# ECG_Combined.net
KiCad netlist of a schematic drawn in EAGLE
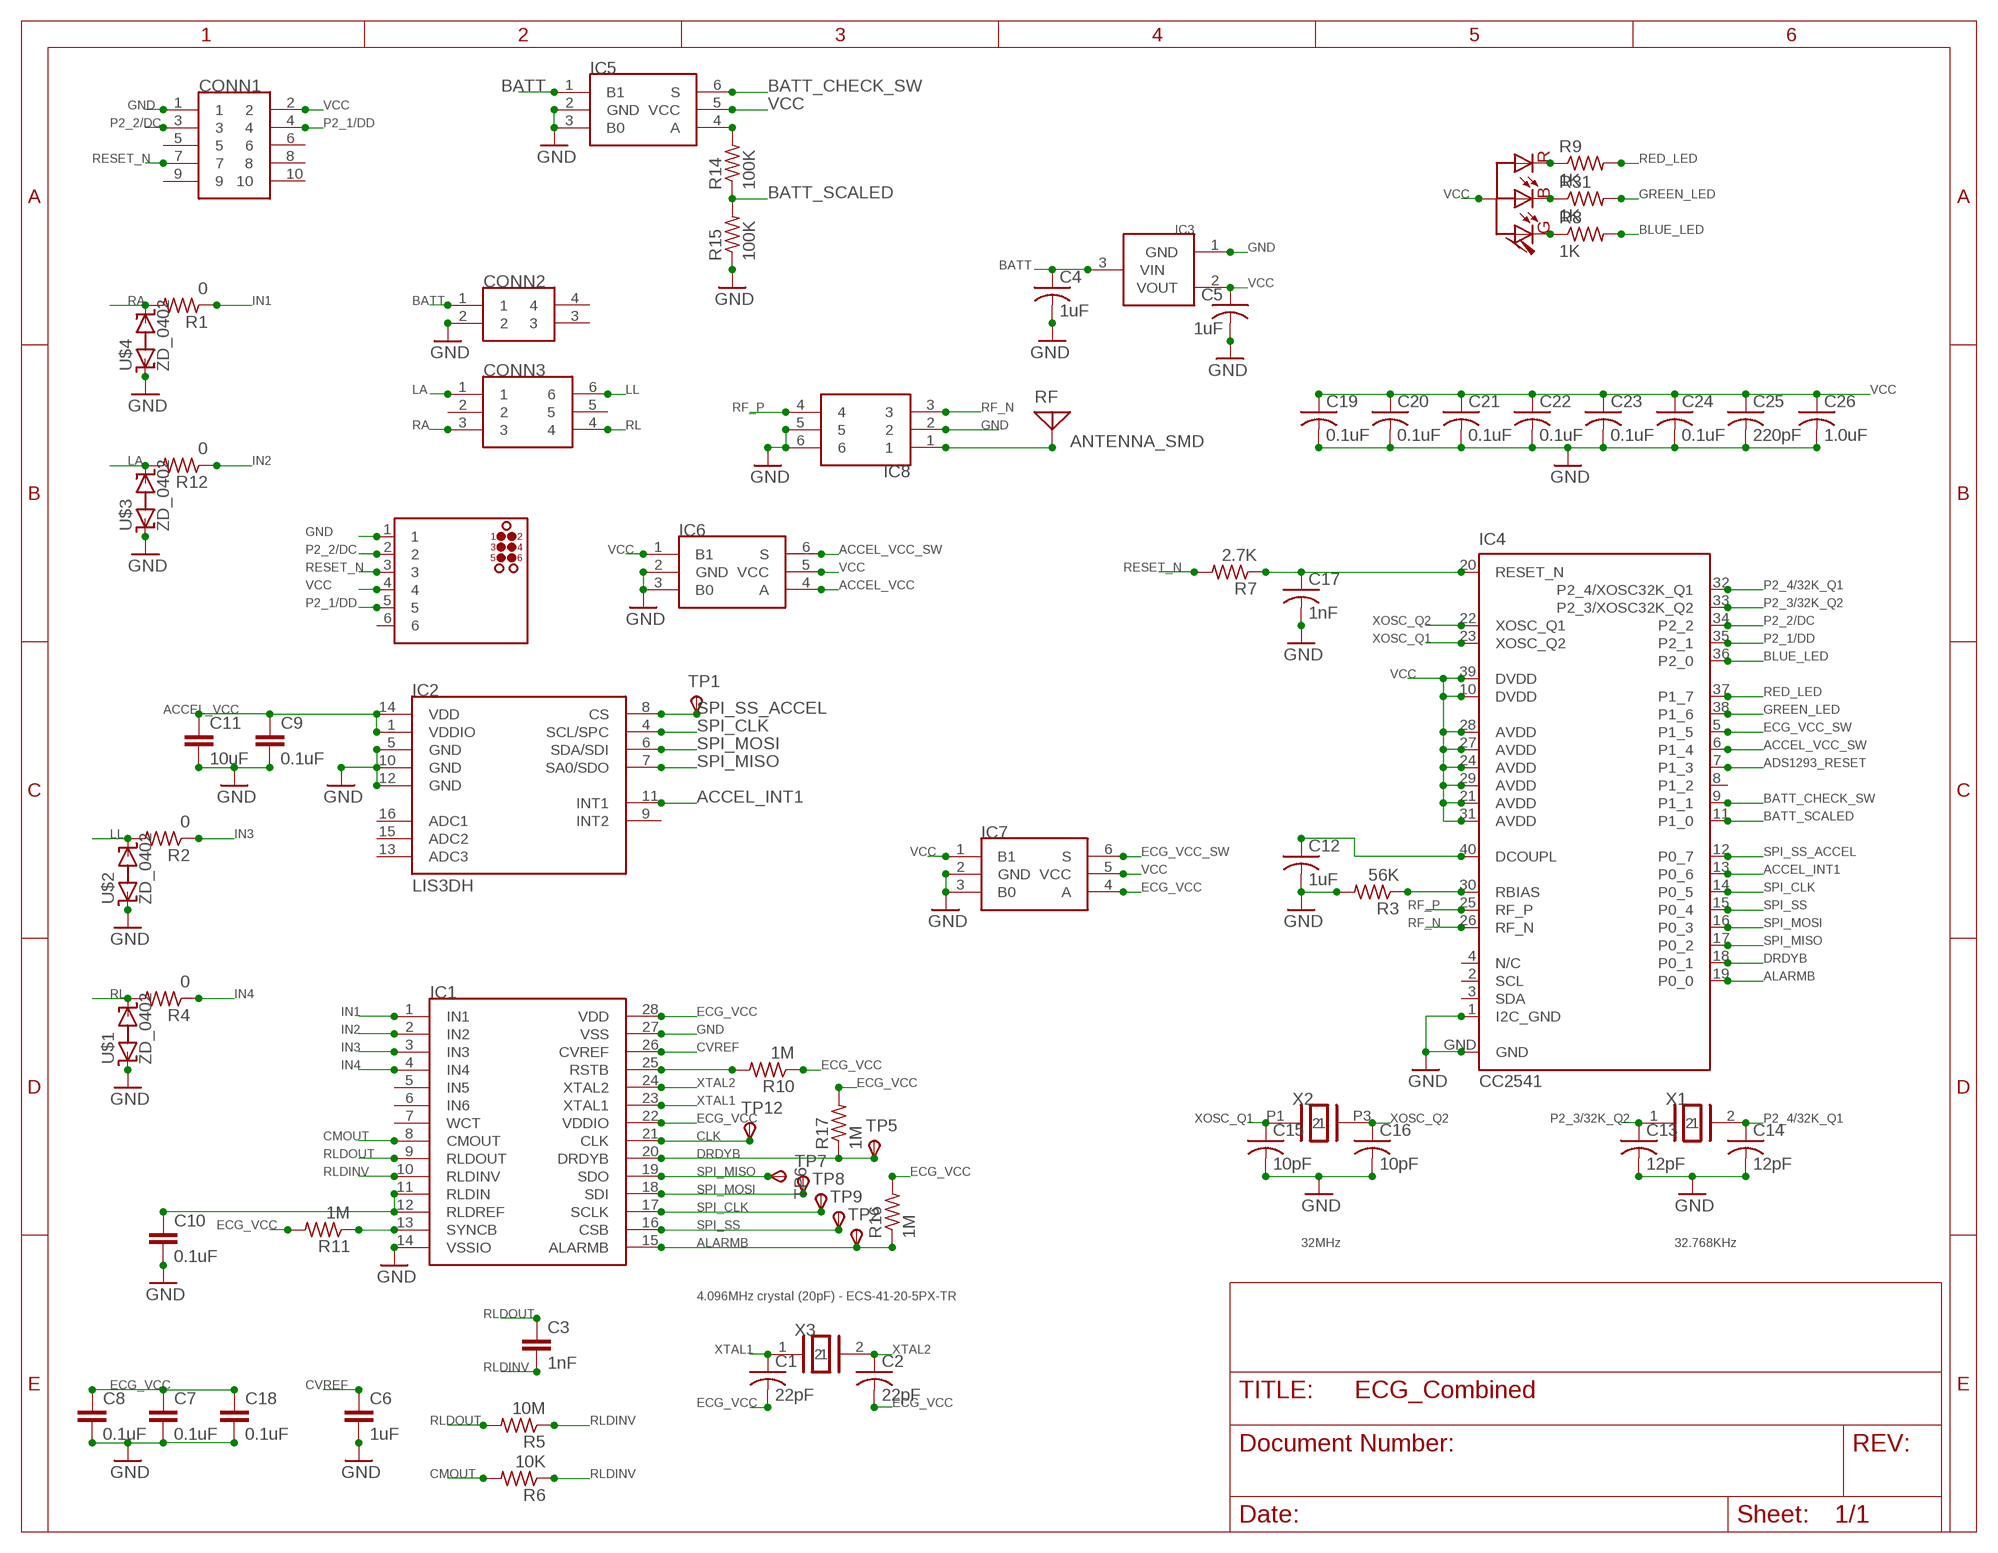
[diagram p0: schematic, sheet 1]

(export (version "E")
  (design (tool "Eeschema 10.0.6"))
  (components
    (comp (ref "C1")
      (value "22pF")
      (footprint "eagle-import:C0201")
      (libsource (lib "eagle-import") (part "C-USC0201"))
    )
    (comp (ref "C2")
      (value "22pF")
      (footprint "eagle-import:C0201")
      (libsource (lib "eagle-import") (part "C-USC0201"))
    )
    (comp (ref "C3")
      (value "1nF")
      (footprint "eagle-import:C0201")
      (libsource (lib "eagle-import") (part "C-EUC0201"))
    )
    (comp (ref "C4")
      (value "1uF")
      (footprint "eagle-import:C0201")
      (libsource (lib "eagle-import") (part "C-USC0201"))
    )
    (comp (ref "C5")
      (value "1uF")
      (footprint "eagle-import:C0201")
      (libsource (lib "eagle-import") (part "C-USC0201"))
    )
    (comp (ref "C6")
      (value "1uF")
      (footprint "eagle-import:C0201")
      (libsource (lib "eagle-import") (part "C-EUC0201"))
    )
    (comp (ref "C7")
      (value "0.1uF")
      (footprint "eagle-import:C0201")
      (libsource (lib "eagle-import") (part "C-EUC0201"))
    )
    (comp (ref "C8")
      (value "0.1uF")
      (footprint "eagle-import:C0201")
      (libsource (lib "eagle-import") (part "C-EUC0201"))
    )
    (comp (ref "C9")
      (value "0.1uF")
      (footprint "eagle-import:C0201")
      (libsource (lib "eagle-import") (part "C-EUC0201"))
    )
    (comp (ref "C10")
      (value "0.1uF")
      (footprint "eagle-import:C0201")
      (libsource (lib "eagle-import") (part "C-EUC0201"))
    )
    (comp (ref "C11")
      (value "10uF")
      (footprint "eagle-import:C0402")
      (libsource (lib "eagle-import") (part "C-EUC0402"))
    )
    (comp (ref "C12")
      (value "1uF")
      (footprint "eagle-import:C0201")
      (libsource (lib "eagle-import") (part "C-USC0201"))
    )
    (comp (ref "C13")
      (value "12pF")
      (footprint "eagle-import:C0201")
      (libsource (lib "eagle-import") (part "C-USC0201"))
    )
    (comp (ref "C14")
      (value "12pF")
      (footprint "eagle-import:C0201")
      (libsource (lib "eagle-import") (part "C-USC0201"))
    )
    (comp (ref "C15")
      (value "10pF")
      (footprint "eagle-import:C0201")
      (libsource (lib "eagle-import") (part "C-USC0201"))
    )
    (comp (ref "C16")
      (value "10pF")
      (footprint "eagle-import:C0201")
      (libsource (lib "eagle-import") (part "C-USC0201"))
    )
    (comp (ref "C17")
      (value "1nF")
      (footprint "eagle-import:C0201")
      (libsource (lib "eagle-import") (part "C-USC0201"))
    )
    (comp (ref "C18")
      (value "0.1uF")
      (footprint "eagle-import:C0201")
      (libsource (lib "eagle-import") (part "C-EUC0201"))
    )
    (comp (ref "C19")
      (value "0.1uF")
      (footprint "eagle-import:C0201")
      (libsource (lib "eagle-import") (part "C-USC0201"))
    )
    (comp (ref "C20")
      (value "0.1uF")
      (footprint "eagle-import:C0201")
      (libsource (lib "eagle-import") (part "C-USC0201"))
    )
    (comp (ref "C21")
      (value "0.1uF")
      (footprint "eagle-import:C0201")
      (libsource (lib "eagle-import") (part "C-USC0201"))
    )
    (comp (ref "C22")
      (value "0.1uF")
      (footprint "eagle-import:C0201")
      (libsource (lib "eagle-import") (part "C-USC0201"))
    )
    (comp (ref "C23")
      (value "0.1uF")
      (footprint "eagle-import:C0201")
      (libsource (lib "eagle-import") (part "C-USC0201"))
    )
    (comp (ref "C24")
      (value "0.1uF")
      (footprint "eagle-import:C0201")
      (libsource (lib "eagle-import") (part "C-USC0201"))
    )
    (comp (ref "C25")
      (value "220pF")
      (footprint "eagle-import:C0201")
      (libsource (lib "eagle-import") (part "C-USC0201"))
    )
    (comp (ref "C26")
      (value "1.0uF")
      (footprint "eagle-import:C0201")
      (libsource (lib "eagle-import") (part "C-USC0201"))
    )
    (comp (ref "CONN1")
      (value "10POS_1.27MM_SMD")
      (footprint "eagle-import:1.27MM_SMD")
      (libsource (lib "eagle-import") (part "10POS_1.27MM_SMD"))
    )
    (comp (ref "CONN2")
      (value "M80-4V")
      (footprint "eagle-import:M80-4-V")
      (libsource (lib "eagle-import") (part "M80-4V"))
    )
    (comp (ref "CONN3")
      (value "M80-6V")
      (footprint "eagle-import:M80-6-V")
      (libsource (lib "eagle-import") (part "M80-6V"))
    )
    (comp (ref "IC1")
      (value "ADS1293")
      (footprint "eagle-import:WQFN28")
      (libsource (lib "eagle-import") (part "ADS1293"))
    )
    (comp (ref "IC2")
      (value "LIS3DH")
      (footprint "eagle-import:LGA16-3MM")
      (libsource (lib "eagle-import") (part "LIS3DH"))
    )
    (comp (ref "IC3")
      (value "MCP1703")
      (footprint "eagle-import:SOT23")
      (libsource (lib "eagle-import") (part "MCP1703"))
    )
    (comp (ref "IC4")
      (value "CC2541")
      (footprint "eagle-import:RHA_S-PVQFN-N40")
      (libsource (lib "eagle-import") (part "CC2541"))
    )
    (comp (ref "IC5")
      (value "FSA4157")
      (footprint "eagle-import:SC70-6")
      (libsource (lib "eagle-import") (part "FSA4157"))
    )
    (comp (ref "IC6")
      (value "FSA4157")
      (footprint "eagle-import:SC70-6")
      (libsource (lib "eagle-import") (part "FSA4157"))
    )
    (comp (ref "IC7")
      (value "FSA4157")
      (footprint "eagle-import:SC70-6")
      (libsource (lib "eagle-import") (part "FSA4157"))
    )
    (comp (ref "IC8")
      (value "BALUN_2450BM_SERIES_SMD")
      (footprint "eagle-import:BALUN_SMD_2450BM_SERIES")
      (libsource (lib "eagle-import") (part "BALUN_2450BM_SERIES_SMD"))
    )
    (comp (ref "R1")
      (value "0")
      (footprint "eagle-import:R0201")
      (libsource (lib "eagle-import") (part "R-US_R0201"))
    )
    (comp (ref "R2")
      (value "0")
      (footprint "eagle-import:R0201")
      (libsource (lib "eagle-import") (part "R-US_R0201"))
    )
    (comp (ref "R3")
      (value "56K")
      (footprint "eagle-import:R0201")
      (libsource (lib "eagle-import") (part "R-US_R0201"))
    )
    (comp (ref "R4")
      (value "0")
      (footprint "eagle-import:R0201")
      (libsource (lib "eagle-import") (part "R-US_R0201"))
    )
    (comp (ref "R5")
      (value "10M")
      (footprint "eagle-import:R0201")
      (libsource (lib "eagle-import") (part "R-US_R0201"))
    )
    (comp (ref "R6")
      (value "10K")
      (footprint "eagle-import:R0201")
      (libsource (lib "eagle-import") (part "R-US_R0201"))
    )
    (comp (ref "R7")
      (value "2.7K")
      (footprint "eagle-import:R0201")
      (libsource (lib "eagle-import") (part "R-US_R0201"))
    )
    (comp (ref "R8")
      (value "1K")
      (footprint "eagle-import:R0201")
      (libsource (lib "eagle-import") (part "R-US_R0201"))
    )
    (comp (ref "R9")
      (value "1K")
      (footprint "eagle-import:R0201")
      (libsource (lib "eagle-import") (part "R-US_R0201"))
    )
    (comp (ref "R10")
      (value "1M")
      (footprint "eagle-import:R0201")
      (libsource (lib "eagle-import") (part "R-US_R0201"))
    )
    (comp (ref "R11")
      (value "1M")
      (footprint "eagle-import:R0201")
      (libsource (lib "eagle-import") (part "R-US_R0201"))
    )
    (comp (ref "R12")
      (value "0")
      (footprint "eagle-import:R0201")
      (libsource (lib "eagle-import") (part "R-US_R0201"))
    )
    (comp (ref "R14")
      (value "100K")
      (footprint "eagle-import:R0201")
      (libsource (lib "eagle-import") (part "R-US_R0201"))
    )
    (comp (ref "R15")
      (value "100K")
      (footprint "eagle-import:R0201")
      (libsource (lib "eagle-import") (part "R-US_R0201"))
    )
    (comp (ref "R16")
      (value "1M")
      (footprint "eagle-import:R0201")
      (libsource (lib "eagle-import") (part "R-US_R0201"))
    )
    (comp (ref "R17")
      (value "1M")
      (footprint "eagle-import:R0201")
      (libsource (lib "eagle-import") (part "R-US_R0201"))
    )
    (comp (ref "R31")
      (value "1K")
      (footprint "eagle-import:R0201")
      (libsource (lib "eagle-import") (part "R-US_R0201"))
    )
    (comp (ref "RF")
      (value "ANTENNA_SMD")
      (footprint "eagle-import:ANTENNA_SMD")
      (libsource (lib "eagle-import") (part "ANTENNA_SMD"))
    )
    (comp (ref "TP1")
      (value "TPSTP08SQ")
      (footprint "eagle-import:TP08SQ")
      (libsource (lib "eagle-import") (part "TPSTP08SQ"))
    )
    (comp (ref "TP2")
      (value "TPSTP06R")
      (footprint "eagle-import:TP06R")
      (libsource (lib "eagle-import") (part "TPSTP06R"))
    )
    (comp (ref "TP5")
      (value "TPSTP08SQ")
      (footprint "eagle-import:TP08SQ")
      (libsource (lib "eagle-import") (part "TPSTP08SQ"))
    )
    (comp (ref "TP6")
      (value "TPSTP08SQ")
      (footprint "eagle-import:TP08SQ")
      (libsource (lib "eagle-import") (part "TPSTP08SQ"))
    )
    (comp (ref "TP7")
      (value "TPSTP08SQ")
      (footprint "eagle-import:TP08SQ")
      (libsource (lib "eagle-import") (part "TPSTP08SQ"))
    )
    (comp (ref "TP8")
      (value "TPSTP08SQ")
      (footprint "eagle-import:TP08SQ")
      (libsource (lib "eagle-import") (part "TPSTP08SQ"))
    )
    (comp (ref "TP9")
      (value "TPSTP08SQ")
      (footprint "eagle-import:TP08SQ")
      (libsource (lib "eagle-import") (part "TPSTP08SQ"))
    )
    (comp (ref "TP12")
      (value "TPSTP06R")
      (footprint "eagle-import:TP06R")
      (libsource (lib "eagle-import") (part "TPSTP06R"))
    )
    (comp (ref "TRI_LED")
      (value "SML-LX0404SIUPGUSB")
      (footprint "eagle-import:SML-LX0404SIUPGUSB")
      (libsource (lib "eagle-import") (part "SML-LX0404SIUPGUSB"))
    )
    (comp (ref "U$1")
      (value "ZD_0402")
      (footprint "eagle-import:0402")
      (libsource (lib "eagle-import") (part "ZD_0402"))
    )
    (comp (ref "U$2")
      (value "ZD_0402")
      (footprint "eagle-import:0402")
      (libsource (lib "eagle-import") (part "ZD_0402"))
    )
    (comp (ref "U$3")
      (value "ZD_0402")
      (footprint "eagle-import:0402")
      (libsource (lib "eagle-import") (part "ZD_0402"))
    )
    (comp (ref "U$4")
      (value "ZD_0402")
      (footprint "eagle-import:0402")
      (libsource (lib "eagle-import") (part "ZD_0402"))
    )
    (comp (ref "U$5")
      (value "TC2030-MCP-NL")
      (footprint "eagle-import:TC2030-MCP-NL")
      (libsource (lib "eagle-import") (part "TC2030-MCP-NL"))
    )
    (comp (ref "X1")
      (value "XTAL-2SMD")
      (footprint "eagle-import:2-SMD")
      (libsource (lib "eagle-import") (part "XTAL-2SMD"))
    )
    (comp (ref "X2")
      (value "XTAL_403")
      (footprint "eagle-import:4-SMD")
      (libsource (lib "eagle-import") (part "XTAL_403"))
    )
    (comp (ref "X3")
      (value "XTAL-CSM7")
      (footprint "eagle-import:CSM-7")
      (libsource (lib "eagle-import") (part "XTAL-CSM7"))
    )
  )
  (nets
    (net (code "1") (name "/ACCEL_INT1") (class "Default")
      (node (ref "IC2") (pin "11") (pinfunction "INT1_11") (pintype "bidirectional"))
      (node (ref "IC4") (pin "13") (pinfunction "P0_6_13") (pintype "bidirectional"))
    )
    (net (code "2") (name "/ACCEL_VCC") (class "Default")
      (node (ref "C11") (pin "1") (pinfunction "1_1") (pintype "passive"))
      (node (ref "C9") (pin "1") (pinfunction "1_1") (pintype "passive"))
      (node (ref "IC2") (pin "1") (pinfunction "VDDIO_1") (pintype "bidirectional"))
      (node (ref "IC2") (pin "14") (pinfunction "VDD_14") (pintype "bidirectional"))
      (node (ref "IC6") (pin "4") (pinfunction "A_4") (pintype "bidirectional"))
    )
    (net (code "3") (name "/ACCEL_VCC_SW") (class "Default")
      (node (ref "IC4") (pin "6") (pinfunction "P1_4_6") (pintype "bidirectional"))
      (node (ref "IC6") (pin "6") (pinfunction "S_6") (pintype "bidirectional"))
    )
    (net (code "4") (name "/ADS1293_RESET") (class "Default")
      (node (ref "IC4") (pin "7") (pinfunction "P1_3_7") (pintype "bidirectional"))
    )
    (net (code "5") (name "/ALARMB") (class "Default")
      (node (ref "IC1") (pin "15") (pinfunction "ALARMB_15") (pintype "bidirectional"))
      (node (ref "IC4") (pin "19") (pinfunction "P0_0_19") (pintype "bidirectional"))
      (node (ref "R16") (pin "1") (pinfunction "1_1") (pintype "passive"))
      (node (ref "TP2") (pin "TP") (pinfunction "PP_TP") (pintype "input"))
    )
    (net (code "6") (name "/BATT") (class "Default")
      (node (ref "C4") (pin "1") (pinfunction "1_1") (pintype "passive"))
      (node (ref "CONN2") (pin "1") (pinfunction "1_1") (pintype "bidirectional"))
      (node (ref "IC3") (pin "3") (pinfunction "VIN_3") (pintype "bidirectional"))
      (node (ref "IC5") (pin "1") (pinfunction "B1_1") (pintype "bidirectional"))
    )
    (net (code "7") (name "/BATT_CHECK_SW") (class "Default")
      (node (ref "IC4") (pin "9") (pinfunction "P1_1_9") (pintype "bidirectional"))
      (node (ref "IC5") (pin "6") (pinfunction "S_6") (pintype "bidirectional"))
    )
    (net (code "8") (name "/BATT_SCALED") (class "Default")
      (node (ref "IC4") (pin "11") (pinfunction "P1_0_11") (pintype "bidirectional"))
      (node (ref "R14") (pin "1") (pinfunction "1_1") (pintype "passive"))
      (node (ref "R15") (pin "2") (pinfunction "2_2") (pintype "passive"))
    )
    (net (code "9") (name "/BLUE_LED") (class "Default")
      (node (ref "IC4") (pin "36") (pinfunction "P2_0_36") (pintype "bidirectional"))
      (node (ref "R8") (pin "2") (pinfunction "2_2") (pintype "passive"))
    )
    (net (code "10") (name "/CLK") (class "Default")
      (node (ref "IC1") (pin "21") (pinfunction "CLK_21") (pintype "bidirectional"))
      (node (ref "TP12") (pin "TP") (pinfunction "PP_TP") (pintype "input"))
    )
    (net (code "11") (name "/CMOUT") (class "Default")
      (node (ref "IC1") (pin "8") (pinfunction "CMOUT_8") (pintype "bidirectional"))
      (node (ref "R6") (pin "2") (pinfunction "2_2") (pintype "passive"))
    )
    (net (code "12") (name "/CVREF") (class "Default")
      (node (ref "C6") (pin "1") (pinfunction "1_1") (pintype "passive"))
      (node (ref "IC1") (pin "26") (pinfunction "CVREF_26") (pintype "bidirectional"))
    )
    (net (code "13") (name "/DRDYB") (class "Default")
      (node (ref "IC1") (pin "20") (pinfunction "DRDYB_20") (pintype "bidirectional"))
      (node (ref "IC4") (pin "18") (pinfunction "P0_1_18") (pintype "bidirectional"))
      (node (ref "R17") (pin "1") (pinfunction "1_1") (pintype "passive"))
      (node (ref "TP5") (pin "TP") (pinfunction "PP_TP") (pintype "input"))
    )
    (net (code "14") (name "/ECG_VCC") (class "Default")
      (node (ref "C1") (pin "2") (pinfunction "2_2") (pintype "passive"))
      (node (ref "C18") (pin "1") (pinfunction "1_1") (pintype "passive"))
      (node (ref "C2") (pin "2") (pinfunction "2_2") (pintype "passive"))
      (node (ref "C7") (pin "1") (pinfunction "1_1") (pintype "passive"))
      (node (ref "C8") (pin "1") (pinfunction "1_1") (pintype "passive"))
      (node (ref "IC1") (pin "22") (pinfunction "VDDIO_22") (pintype "bidirectional"))
      (node (ref "IC1") (pin "28") (pinfunction "VDD_28") (pintype "bidirectional"))
      (node (ref "IC7") (pin "4") (pinfunction "A_4") (pintype "bidirectional"))
      (node (ref "R10") (pin "1") (pinfunction "1_1") (pintype "passive"))
      (node (ref "R11") (pin "2") (pinfunction "2_2") (pintype "passive"))
      (node (ref "R16") (pin "2") (pinfunction "2_2") (pintype "passive"))
      (node (ref "R17") (pin "2") (pinfunction "2_2") (pintype "passive"))
    )
    (net (code "15") (name "/ECG_VCC_SW") (class "Default")
      (node (ref "IC4") (pin "5") (pinfunction "P1_5_5") (pintype "bidirectional"))
      (node (ref "IC7") (pin "6") (pinfunction "S_6") (pintype "bidirectional"))
    )
    (net (code "16") (name "/GREEN_LED") (class "Default")
      (node (ref "IC4") (pin "38") (pinfunction "P1_6_38") (pintype "bidirectional"))
      (node (ref "R31") (pin "2") (pinfunction "2_2") (pintype "passive"))
    )
    (net (code "17") (name "/IN1") (class "Default")
      (node (ref "IC1") (pin "1") (pinfunction "IN1_1") (pintype "bidirectional"))
      (node (ref "R1") (pin "1") (pinfunction "1_1") (pintype "passive"))
    )
    (net (code "18") (name "/IN2") (class "Default")
      (node (ref "IC1") (pin "2") (pinfunction "IN2_2") (pintype "bidirectional"))
      (node (ref "R12") (pin "1") (pinfunction "1_1") (pintype "passive"))
    )
    (net (code "19") (name "/IN3") (class "Default")
      (node (ref "IC1") (pin "3") (pinfunction "IN3_3") (pintype "bidirectional"))
      (node (ref "R2") (pin "1") (pinfunction "1_1") (pintype "passive"))
    )
    (net (code "20") (name "/IN4") (class "Default")
      (node (ref "IC1") (pin "4") (pinfunction "IN4_4") (pintype "bidirectional"))
      (node (ref "R4") (pin "1") (pinfunction "1_1") (pintype "passive"))
    )
    (net (code "21") (name "/LA") (class "Default")
      (node (ref "CONN3") (pin "1") (pinfunction "1_1") (pintype "bidirectional"))
      (node (ref "R12") (pin "2") (pinfunction "2_2") (pintype "passive"))
      (node (ref "U$3") (pin "2") (pinfunction "C_2") (pintype "passive"))
    )
    (net (code "22") (name "/LL") (class "Default")
      (node (ref "CONN3") (pin "6") (pinfunction "6_6") (pintype "bidirectional"))
      (node (ref "R2") (pin "2") (pinfunction "2_2") (pintype "passive"))
      (node (ref "U$2") (pin "2") (pinfunction "C_2") (pintype "passive"))
    )
    (net (code "23") (name "/N{slash}C") (class "Default")
      (node (ref "IC4") (pin "4") (pinfunction "N/C_4") (pintype "power_in"))
    )
    (net (code "24") (name "/P2_1{slash}DD") (class "Default")
      (node (ref "CONN1") (pin "4") (pinfunction "4_4") (pintype "bidirectional"))
      (node (ref "IC4") (pin "35") (pinfunction "P2_1_35") (pintype "bidirectional"))
      (node (ref "U$5") (pin "5") (pinfunction "5_5") (pintype "output"))
    )
    (net (code "25") (name "/P2_2{slash}DC") (class "Default")
      (node (ref "CONN1") (pin "3") (pinfunction "3_3") (pintype "bidirectional"))
      (node (ref "IC4") (pin "34") (pinfunction "P2_2_34") (pintype "bidirectional"))
      (node (ref "U$5") (pin "2") (pinfunction "2_2") (pintype "power_in"))
    )
    (net (code "26") (name "/P2_3{slash}32K_Q2") (class "Default")
      (node (ref "C13") (pin "1") (pinfunction "1_1") (pintype "passive"))
      (node (ref "IC4") (pin "33") (pinfunction "P2_3/XOSC32K_Q2_33") (pintype "bidirectional"))
      (node (ref "X1") (pin "1") (pinfunction "1_1") (pintype "bidirectional"))
    )
    (net (code "27") (name "/P2_4{slash}32K_Q1") (class "Default")
      (node (ref "C14") (pin "1") (pinfunction "1_1") (pintype "passive"))
      (node (ref "IC4") (pin "32") (pinfunction "P2_4/XOSC32K_Q1_32") (pintype "bidirectional"))
      (node (ref "X1") (pin "2") (pinfunction "2_2") (pintype "bidirectional"))
    )
    (net (code "28") (name "/RA") (class "Default")
      (node (ref "CONN3") (pin "3") (pinfunction "3_3") (pintype "bidirectional"))
      (node (ref "R1") (pin "2") (pinfunction "2_2") (pintype "passive"))
      (node (ref "U$4") (pin "2") (pinfunction "C_2") (pintype "passive"))
    )
    (net (code "29") (name "/RED_LED") (class "Default")
      (node (ref "IC4") (pin "37") (pinfunction "P1_7_37") (pintype "bidirectional"))
      (node (ref "R9") (pin "2") (pinfunction "2_2") (pintype "passive"))
    )
    (net (code "30") (name "/RESET_N") (class "Default")
      (node (ref "CONN1") (pin "7") (pinfunction "7_7") (pintype "bidirectional"))
      (node (ref "R7") (pin "2") (pinfunction "2_2") (pintype "passive"))
      (node (ref "U$5") (pin "3") (pinfunction "3_3") (pintype "power_in"))
    )
    (net (code "31") (name "/RF_N") (class "Default")
      (node (ref "IC4") (pin "26") (pinfunction "RF_N_26") (pintype "bidirectional"))
      (node (ref "IC8") (pin "3") (pinfunction "3_3") (pintype "bidirectional"))
    )
    (net (code "32") (name "/RF_P") (class "Default")
      (node (ref "IC4") (pin "25") (pinfunction "RF_P_25") (pintype "bidirectional"))
      (node (ref "IC8") (pin "4") (pinfunction "4_4") (pintype "bidirectional"))
    )
    (net (code "33") (name "/RL") (class "Default")
      (node (ref "CONN3") (pin "4") (pinfunction "4_4") (pintype "bidirectional"))
      (node (ref "R4") (pin "2") (pinfunction "2_2") (pintype "passive"))
      (node (ref "U$1") (pin "2") (pinfunction "C_2") (pintype "passive"))
    )
    (net (code "34") (name "/RLDINV") (class "Default")
      (node (ref "C3") (pin "2") (pinfunction "2_2") (pintype "passive"))
      (node (ref "IC1") (pin "10") (pinfunction "RLDINV_10") (pintype "bidirectional"))
      (node (ref "R5") (pin "1") (pinfunction "1_1") (pintype "passive"))
      (node (ref "R6") (pin "1") (pinfunction "1_1") (pintype "passive"))
    )
    (net (code "35") (name "/RLDOUT") (class "Default")
      (node (ref "C3") (pin "1") (pinfunction "1_1") (pintype "passive"))
      (node (ref "IC1") (pin "9") (pinfunction "RLDOUT_9") (pintype "bidirectional"))
      (node (ref "R5") (pin "2") (pinfunction "2_2") (pintype "passive"))
    )
    (net (code "36") (name "/SPI_CLK") (class "Default")
      (node (ref "IC1") (pin "17") (pinfunction "SCLK_17") (pintype "bidirectional"))
      (node (ref "IC2") (pin "4") (pinfunction "SCL/SPC_4") (pintype "bidirectional"))
      (node (ref "IC4") (pin "14") (pinfunction "P0_5_14") (pintype "bidirectional"))
      (node (ref "TP8") (pin "TP") (pinfunction "PP_TP") (pintype "input"))
    )
    (net (code "37") (name "/SPI_MISO") (class "Default")
      (node (ref "IC1") (pin "19") (pinfunction "SDO_19") (pintype "bidirectional"))
      (node (ref "IC2") (pin "7") (pinfunction "SA0/SDO_7") (pintype "bidirectional"))
      (node (ref "IC4") (pin "17") (pinfunction "P0_2_17") (pintype "bidirectional"))
      (node (ref "TP6") (pin "TP") (pinfunction "PP_TP") (pintype "input"))
    )
    (net (code "38") (name "/SPI_MOSI") (class "Default")
      (node (ref "IC1") (pin "18") (pinfunction "SDI_18") (pintype "bidirectional"))
      (node (ref "IC2") (pin "6") (pinfunction "SDA/SDI_6") (pintype "bidirectional"))
      (node (ref "IC4") (pin "16") (pinfunction "P0_3_16") (pintype "bidirectional"))
      (node (ref "TP7") (pin "TP") (pinfunction "PP_TP") (pintype "input"))
    )
    (net (code "39") (name "/SPI_SS") (class "Default")
      (node (ref "IC1") (pin "16") (pinfunction "CSB_16") (pintype "bidirectional"))
      (node (ref "IC4") (pin "15") (pinfunction "P0_4_15") (pintype "bidirectional"))
      (node (ref "TP9") (pin "TP") (pinfunction "PP_TP") (pintype "input"))
    )
    (net (code "40") (name "/SPI_SS_ACCEL") (class "Default")
      (node (ref "IC2") (pin "8") (pinfunction "CS_8") (pintype "bidirectional"))
      (node (ref "IC4") (pin "12") (pinfunction "P0_7_12") (pintype "bidirectional"))
      (node (ref "TP1") (pin "TP") (pinfunction "PP_TP") (pintype "input"))
    )
    (net (code "41") (name "/VCC") (class "Default")
      (node (ref "C19") (pin "1") (pinfunction "1_1") (pintype "passive"))
      (node (ref "C20") (pin "1") (pinfunction "1_1") (pintype "passive"))
      (node (ref "C21") (pin "1") (pinfunction "1_1") (pintype "passive"))
      (node (ref "C22") (pin "1") (pinfunction "1_1") (pintype "passive"))
      (node (ref "C23") (pin "1") (pinfunction "1_1") (pintype "passive"))
      (node (ref "C24") (pin "1") (pinfunction "1_1") (pintype "passive"))
      (node (ref "C25") (pin "1") (pinfunction "1_1") (pintype "passive"))
      (node (ref "C26") (pin "1") (pinfunction "1_1") (pintype "passive"))
      (node (ref "C5") (pin "1") (pinfunction "1_1") (pintype "passive"))
      (node (ref "CONN1") (pin "2") (pinfunction "2_2") (pintype "bidirectional"))
      (node (ref "IC3") (pin "2") (pinfunction "VOUT_2") (pintype "bidirectional"))
      (node (ref "IC4") (pin "10") (pinfunction "DVDD_10") (pintype "power_in"))
      (node (ref "IC4") (pin "21") (pinfunction "AVDD_21") (pintype "power_in"))
      (node (ref "IC4") (pin "24") (pinfunction "AVDD_24") (pintype "power_in"))
      (node (ref "IC4") (pin "27") (pinfunction "AVDD_27") (pintype "power_in"))
      (node (ref "IC4") (pin "28") (pinfunction "AVDD_28") (pintype "power_in"))
      (node (ref "IC4") (pin "29") (pinfunction "AVDD_29") (pintype "power_in"))
      (node (ref "IC4") (pin "31") (pinfunction "AVDD_31") (pintype "power_in"))
      (node (ref "IC4") (pin "39") (pinfunction "DVDD_39") (pintype "power_in"))
      (node (ref "IC5") (pin "5") (pinfunction "VCC_5") (pintype "bidirectional"))
      (node (ref "IC6") (pin "1") (pinfunction "B1_1") (pintype "bidirectional"))
      (node (ref "IC6") (pin "5") (pinfunction "VCC_5") (pintype "bidirectional"))
      (node (ref "IC7") (pin "1") (pinfunction "B1_1") (pintype "bidirectional"))
      (node (ref "IC7") (pin "5") (pinfunction "VCC_5") (pintype "bidirectional"))
      (node (ref "TRI_LED") (pin "1") (pinfunction "A_1") (pintype "passive"))
      (node (ref "U$5") (pin "4") (pinfunction "4_4") (pintype "bidirectional"))
    )
    (net (code "42") (name "/XOSC_Q1") (class "Default")
      (node (ref "C15") (pin "1") (pinfunction "1_1") (pintype "passive"))
      (node (ref "IC4") (pin "23") (pinfunction "XOSC_Q2_23") (pintype "bidirectional"))
      (node (ref "X2") (pin "P1") (pinfunction "1_P1") (pintype "bidirectional"))
    )
    (net (code "43") (name "/XOSC_Q2") (class "Default")
      (node (ref "C16") (pin "1") (pinfunction "1_1") (pintype "passive"))
      (node (ref "IC4") (pin "22") (pinfunction "XOSC_Q1_22") (pintype "bidirectional"))
      (node (ref "X2") (pin "P3") (pinfunction "2_P3") (pintype "bidirectional"))
    )
    (net (code "44") (name "/XTAL1") (class "Default")
      (node (ref "C1") (pin "1") (pinfunction "1_1") (pintype "passive"))
      (node (ref "IC1") (pin "23") (pinfunction "XTAL1_23") (pintype "bidirectional"))
      (node (ref "X3") (pin "1") (pinfunction "1_1") (pintype "bidirectional"))
    )
    (net (code "45") (name "/XTAL2") (class "Default")
      (node (ref "C2") (pin "1") (pinfunction "1_1") (pintype "passive"))
      (node (ref "IC1") (pin "24") (pinfunction "XTAL2_24") (pintype "bidirectional"))
      (node (ref "X3") (pin "2") (pinfunction "2_2") (pintype "bidirectional"))
    )
    (net (code "46") (name "GND") (class "Default")
      (node (ref "C10") (pin "2") (pinfunction "2_2") (pintype "passive"))
      (node (ref "C11") (pin "2") (pinfunction "2_2") (pintype "passive"))
      (node (ref "C12") (pin "2") (pinfunction "2_2") (pintype "passive"))
      (node (ref "C13") (pin "2") (pinfunction "2_2") (pintype "passive"))
      (node (ref "C14") (pin "2") (pinfunction "2_2") (pintype "passive"))
      (node (ref "C15") (pin "2") (pinfunction "2_2") (pintype "passive"))
      (node (ref "C16") (pin "2") (pinfunction "2_2") (pintype "passive"))
      (node (ref "C17") (pin "2") (pinfunction "2_2") (pintype "passive"))
      (node (ref "C18") (pin "2") (pinfunction "2_2") (pintype "passive"))
      (node (ref "C19") (pin "2") (pinfunction "2_2") (pintype "passive"))
      (node (ref "C20") (pin "2") (pinfunction "2_2") (pintype "passive"))
      (node (ref "C21") (pin "2") (pinfunction "2_2") (pintype "passive"))
      (node (ref "C22") (pin "2") (pinfunction "2_2") (pintype "passive"))
      (node (ref "C23") (pin "2") (pinfunction "2_2") (pintype "passive"))
      (node (ref "C24") (pin "2") (pinfunction "2_2") (pintype "passive"))
      (node (ref "C25") (pin "2") (pinfunction "2_2") (pintype "passive"))
      (node (ref "C26") (pin "2") (pinfunction "2_2") (pintype "passive"))
      (node (ref "C4") (pin "2") (pinfunction "2_2") (pintype "passive"))
      (node (ref "C5") (pin "2") (pinfunction "2_2") (pintype "passive"))
      (node (ref "C6") (pin "2") (pinfunction "2_2") (pintype "passive"))
      (node (ref "C7") (pin "2") (pinfunction "2_2") (pintype "passive"))
      (node (ref "C8") (pin "2") (pinfunction "2_2") (pintype "passive"))
      (node (ref "C9") (pin "2") (pinfunction "2_2") (pintype "passive"))
      (node (ref "CONN1") (pin "1") (pinfunction "1_1") (pintype "bidirectional"))
      (node (ref "CONN2") (pin "2") (pinfunction "2_2") (pintype "bidirectional"))
      (node (ref "IC1") (pin "14") (pinfunction "VSSIO_14") (pintype "bidirectional"))
      (node (ref "IC1") (pin "27") (pinfunction "VSS_27") (pintype "bidirectional"))
      (node (ref "IC2") (pin "10") (pinfunction "GND_10") (pintype "bidirectional"))
      (node (ref "IC2") (pin "12") (pinfunction "GND_12") (pintype "bidirectional"))
      (node (ref "IC2") (pin "5") (pinfunction "GND_5") (pintype "bidirectional"))
      (node (ref "IC3") (pin "1") (pinfunction "GND_1") (pintype "bidirectional"))
      (node (ref "IC4") (pin "1") (pinfunction "I2C_GND_1") (pintype "power_in"))
      (node (ref "IC4") (pin "GND") (pinfunction "GND_GND") (pintype "passive"))
      (node (ref "IC5") (pin "2") (pinfunction "GND_2") (pintype "bidirectional"))
      (node (ref "IC5") (pin "3") (pinfunction "B0_3") (pintype "bidirectional"))
      (node (ref "IC6") (pin "2") (pinfunction "GND_2") (pintype "bidirectional"))
      (node (ref "IC6") (pin "3") (pinfunction "B0_3") (pintype "bidirectional"))
      (node (ref "IC7") (pin "2") (pinfunction "GND_2") (pintype "bidirectional"))
      (node (ref "IC7") (pin "3") (pinfunction "B0_3") (pintype "bidirectional"))
      (node (ref "IC8") (pin "2") (pinfunction "2_2") (pintype "bidirectional"))
      (node (ref "IC8") (pin "5") (pinfunction "5_5") (pintype "bidirectional"))
      (node (ref "IC8") (pin "6") (pinfunction "6_6") (pintype "bidirectional"))
      (node (ref "R15") (pin "1") (pinfunction "1_1") (pintype "passive"))
      (node (ref "R3") (pin "2") (pinfunction "2_2") (pintype "passive"))
      (node (ref "U$1") (pin "1") (pinfunction "A_1") (pintype "passive"))
      (node (ref "U$2") (pin "1") (pinfunction "A_1") (pintype "passive"))
      (node (ref "U$3") (pin "1") (pinfunction "A_1") (pintype "passive"))
      (node (ref "U$4") (pin "1") (pinfunction "A_1") (pintype "passive"))
      (node (ref "U$5") (pin "1") (pinfunction "1_1") (pintype "passive"))
    )
    (net (code "47") (name "Net-(IC1-RLDIN)") (class "Default")
      (node (ref "C10") (pin "1") (pinfunction "1_1") (pintype "passive"))
      (node (ref "IC1") (pin "11") (pinfunction "RLDIN_11") (pintype "bidirectional"))
      (node (ref "IC1") (pin "12") (pinfunction "RLDREF_12") (pintype "bidirectional"))
    )
    (net (code "48") (name "Net-(IC1-RSTB)") (class "Default")
      (node (ref "IC1") (pin "25") (pinfunction "RSTB_25") (pintype "bidirectional"))
      (node (ref "R10") (pin "2") (pinfunction "2_2") (pintype "passive"))
    )
    (net (code "49") (name "Net-(IC1-SYNCB)") (class "Default")
      (node (ref "IC1") (pin "13") (pinfunction "SYNCB_13") (pintype "bidirectional"))
      (node (ref "R11") (pin "1") (pinfunction "1_1") (pintype "passive"))
    )
    (net (code "50") (name "Net-(IC4-DCOUPL)") (class "Default")
      (node (ref "C12") (pin "1") (pinfunction "1_1") (pintype "passive"))
      (node (ref "IC4") (pin "40") (pinfunction "DCOUPL_40") (pintype "power_in"))
    )
    (net (code "51") (name "Net-(IC4-RBIAS)") (class "Default")
      (node (ref "IC4") (pin "30") (pinfunction "RBIAS_30") (pintype "bidirectional"))
      (node (ref "R3") (pin "1") (pinfunction "1_1") (pintype "passive"))
    )
    (net (code "52") (name "Net-(IC4-RESET_N)") (class "Default")
      (node (ref "C17") (pin "1") (pinfunction "1_1") (pintype "passive"))
      (node (ref "IC4") (pin "20") (pinfunction "RESET_N_20") (pintype "input"))
      (node (ref "R7") (pin "1") (pinfunction "1_1") (pintype "passive"))
    )
    (net (code "53") (name "Net-(IC5-A)") (class "Default")
      (node (ref "IC5") (pin "4") (pinfunction "A_4") (pintype "bidirectional"))
      (node (ref "R14") (pin "2") (pinfunction "2_2") (pintype "passive"))
    )
    (net (code "54") (name "Net-(IC8-Pad1)") (class "Default")
      (node (ref "IC8") (pin "1") (pinfunction "1_1") (pintype "bidirectional"))
      (node (ref "RF") (pin "1") (pinfunction "1_1") (pintype "output"))
    )
    (net (code "55") (name "Net-(TRI_LED-B)") (class "Default")
      (node (ref "R9") (pin "1") (pinfunction "1_1") (pintype "passive"))
      (node (ref "TRI_LED") (pin "3") (pinfunction "B_3") (pintype "passive"))
    )
    (net (code "56") (name "Net-(TRI_LED-G)") (class "Default")
      (node (ref "R31") (pin "1") (pinfunction "1_1") (pintype "passive"))
      (node (ref "TRI_LED") (pin "4") (pinfunction "G_4") (pintype "passive"))
    )
    (net (code "57") (name "Net-(TRI_LED-R)") (class "Default")
      (node (ref "R8") (pin "1") (pinfunction "1_1") (pintype "passive"))
      (node (ref "TRI_LED") (pin "2") (pinfunction "R_2") (pintype "passive"))
    )
    (net (code "58") (name "unconnected-(CONN1-Pad5)") (class "Default")
      (node (ref "CONN1") (pin "5") (pinfunction "5_5") (pintype "bidirectional"))
    )
    (net (code "59") (name "unconnected-(CONN1-Pad6)") (class "Default")
      (node (ref "CONN1") (pin "6") (pinfunction "6_6") (pintype "bidirectional"))
    )
    (net (code "60") (name "unconnected-(CONN1-Pad8)") (class "Default")
      (node (ref "CONN1") (pin "8") (pinfunction "8_8") (pintype "bidirectional"))
    )
    (net (code "61") (name "unconnected-(CONN1-Pad9)") (class "Default")
      (node (ref "CONN1") (pin "9") (pinfunction "9_9") (pintype "bidirectional"))
    )
    (net (code "62") (name "unconnected-(CONN1-Pad10)") (class "Default")
      (node (ref "CONN1") (pin "10") (pinfunction "10_10") (pintype "bidirectional"))
    )
    (net (code "63") (name "unconnected-(CONN2-Pad3)") (class "Default")
      (node (ref "CONN2") (pin "3") (pinfunction "3_3") (pintype "bidirectional"))
    )
    (net (code "64") (name "unconnected-(CONN2-Pad4)") (class "Default")
      (node (ref "CONN2") (pin "4") (pinfunction "4_4") (pintype "bidirectional"))
    )
    (net (code "65") (name "unconnected-(CONN3-Pad2)") (class "Default")
      (node (ref "CONN3") (pin "2") (pinfunction "2_2") (pintype "bidirectional"))
    )
    (net (code "66") (name "unconnected-(CONN3-Pad5)") (class "Default")
      (node (ref "CONN3") (pin "5") (pinfunction "5_5") (pintype "bidirectional"))
    )
    (net (code "67") (name "unconnected-(IC1-IN5-Pad5)") (class "Default")
      (node (ref "IC1") (pin "5") (pinfunction "IN5_5") (pintype "bidirectional"))
    )
    (net (code "68") (name "unconnected-(IC1-IN6-Pad6)") (class "Default")
      (node (ref "IC1") (pin "6") (pinfunction "IN6_6") (pintype "bidirectional"))
    )
    (net (code "69") (name "unconnected-(IC1-WCT-Pad7)") (class "Default")
      (node (ref "IC1") (pin "7") (pinfunction "WCT_7") (pintype "bidirectional"))
    )
    (net (code "70") (name "unconnected-(IC2-ADC1-Pad16)") (class "Default")
      (node (ref "IC2") (pin "16") (pinfunction "ADC1_16") (pintype "bidirectional"))
    )
    (net (code "71") (name "unconnected-(IC2-ADC2-Pad15)") (class "Default")
      (node (ref "IC2") (pin "15") (pinfunction "ADC2_15") (pintype "bidirectional"))
    )
    (net (code "72") (name "unconnected-(IC2-ADC3-Pad13)") (class "Default")
      (node (ref "IC2") (pin "13") (pinfunction "ADC3_13") (pintype "bidirectional"))
    )
    (net (code "73") (name "unconnected-(IC2-INT2-Pad9)") (class "Default")
      (node (ref "IC2") (pin "9") (pinfunction "INT2_9") (pintype "bidirectional"))
    )
    (net (code "74") (name "unconnected-(IC4-P1_2-Pad8)") (class "Default")
      (node (ref "IC4") (pin "8") (pinfunction "P1_2_8") (pintype "bidirectional"))
    )
    (net (code "75") (name "unconnected-(IC4-SCL-Pad2)") (class "Default")
      (node (ref "IC4") (pin "2") (pinfunction "SCL_2") (pintype "bidirectional"))
    )
    (net (code "76") (name "unconnected-(IC4-SDA-Pad3)") (class "Default")
      (node (ref "IC4") (pin "3") (pinfunction "SDA_3") (pintype "bidirectional"))
    )
    (net (code "77") (name "unconnected-(U$5-Pad6)") (class "Default")
      (node (ref "U$5") (pin "6") (pinfunction "6_6") (pintype "bidirectional"))
    )
  )
)
